# stm32h405-braids.net
KiCad netlist of a schematic drawn in EAGLE
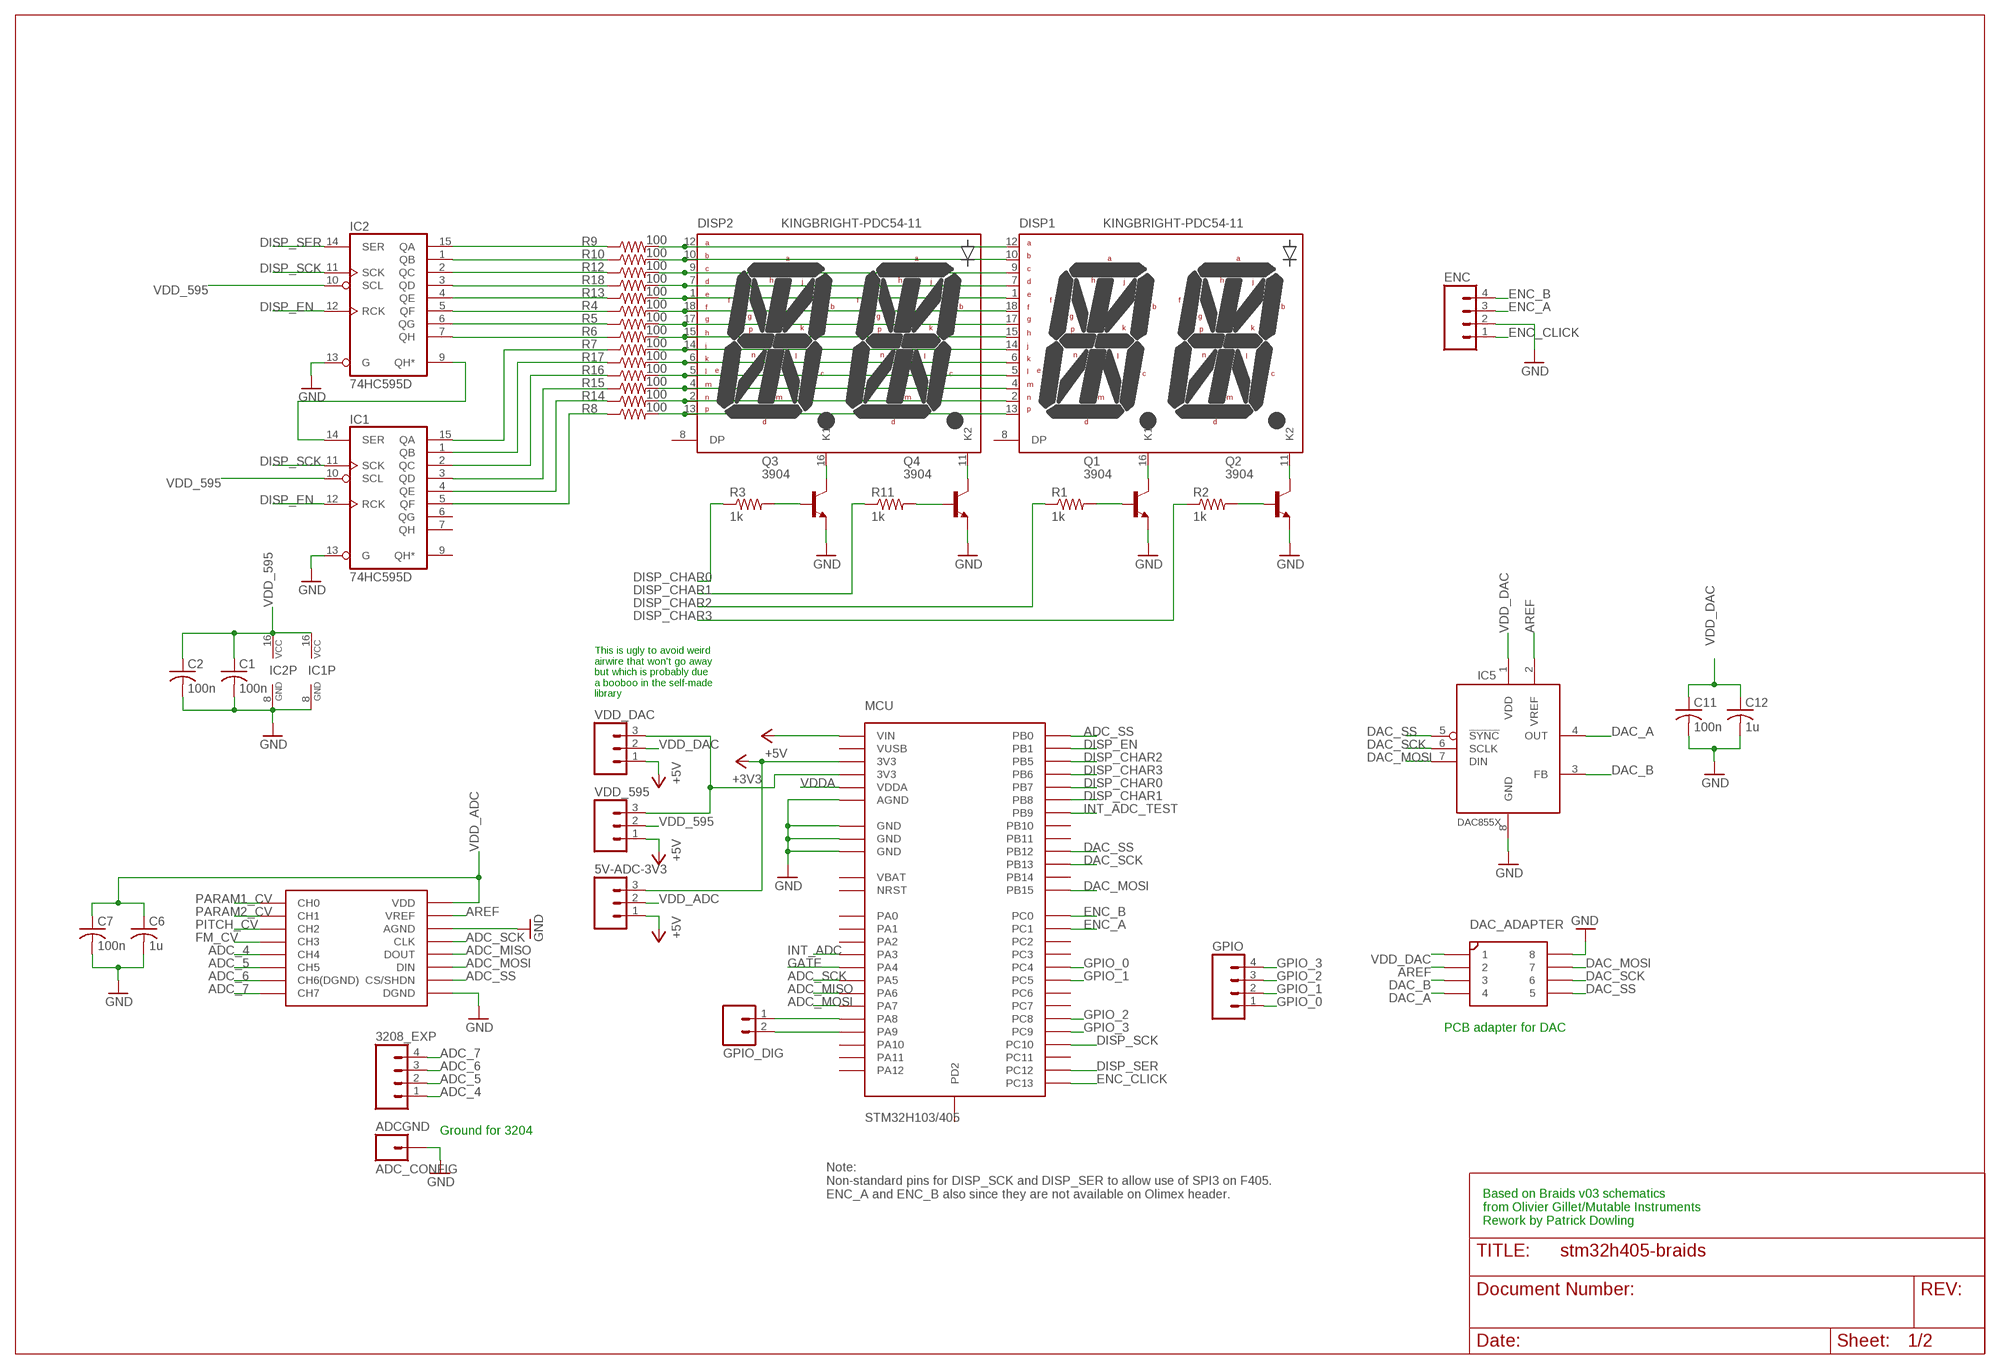
[diagram p0: schematic, sheet 1]
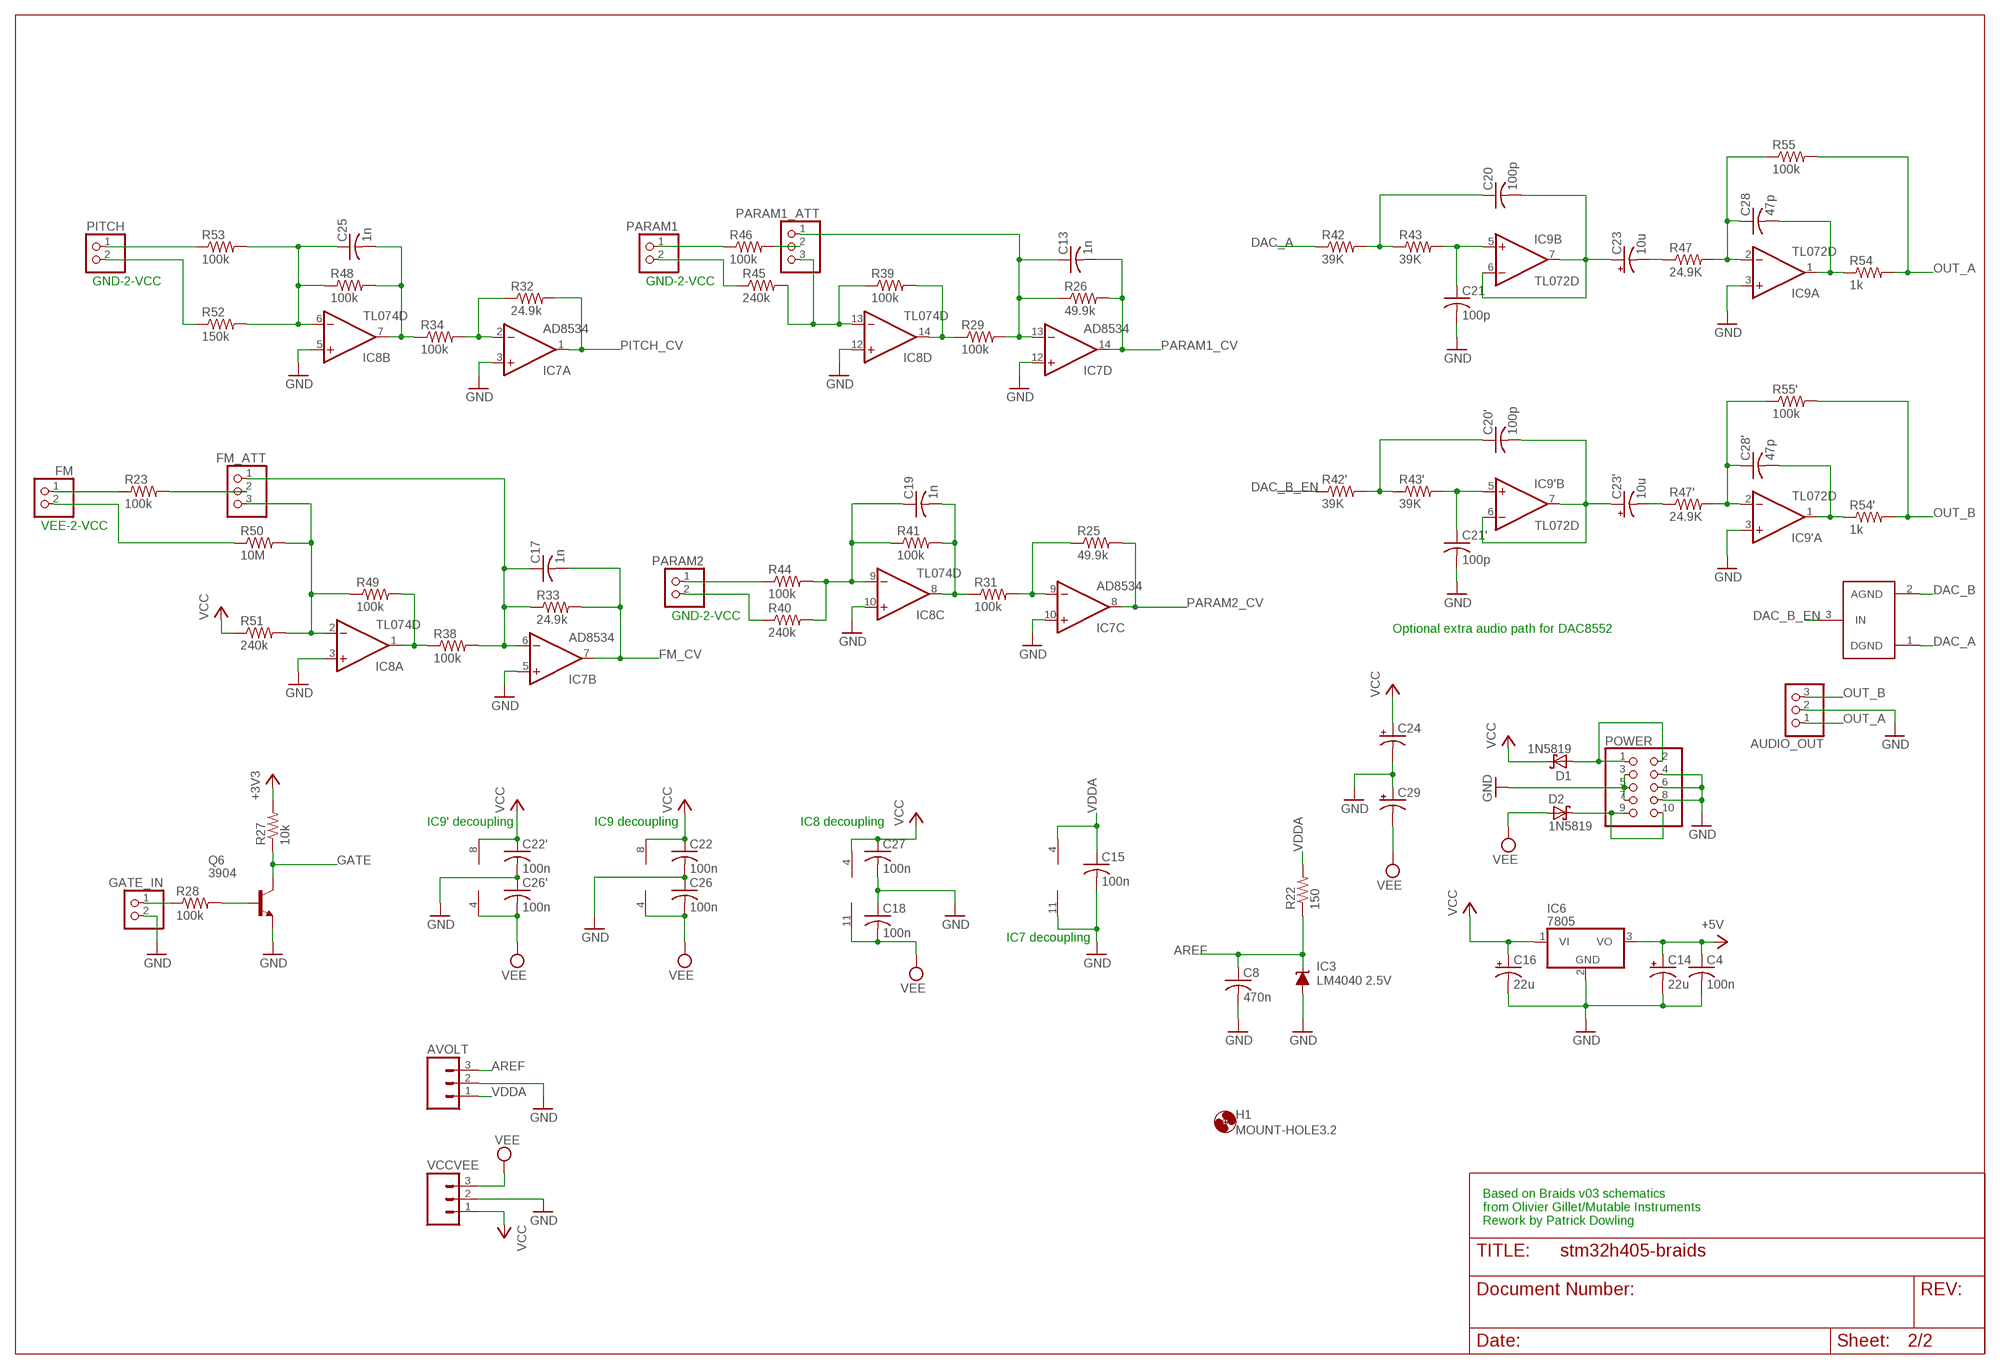
[diagram p1: schematic, sheet 2]

(export (version "E")
  (design (tool "Eeschema 10.0.6"))
  (components
    (comp (ref "AUDIO_OUT")
      (value "PINHD-1X3")
      (footprint "eagle-import:1X03")
      (libsource (lib "eagle-import") (part "PINHD-1X3"))
    )
    (comp (ref "AVOLT")
      (value "M031X03_NO_SILK")
      (footprint "eagle-import:1X03_NO_SILK")
      (libsource (lib "eagle-import") (part "M031X03_NO_SILK"))
    )
    (comp (ref "C4")
      (value "100n")
      (footprint "eagle-import:C025-024X044")
      (libsource (lib "eagle-import") (part "C-US025-024X044"))
    )
    (comp (ref "C8")
      (value "470n")
      (footprint "eagle-import:C0805")
      (libsource (lib "eagle-import") (part "C-USC0805"))
    )
    (comp (ref "C13")
      (value "1n")
      (footprint "eagle-import:C0805")
      (libsource (lib "eagle-import") (part "C-USC0805"))
    )
    (comp (ref "C14")
      (value "22u")
      (footprint "eagle-import:E2,5-6")
      (libsource (lib "eagle-import") (part "CPOL-USE2.5-6"))
    )
    (comp (ref "C15")
      (value "100n")
      (footprint "eagle-import:C0805")
      (libsource (lib "eagle-import") (part "C-USC0805"))
    )
    (comp (ref "C16")
      (value "22u")
      (footprint "eagle-import:E2,5-6")
      (libsource (lib "eagle-import") (part "CPOL-USE2.5-6"))
    )
    (comp (ref "C17")
      (value "1n")
      (footprint "eagle-import:C0805")
      (libsource (lib "eagle-import") (part "C-USC0805"))
    )
    (comp (ref "C18")
      (value "100n")
      (footprint "eagle-import:C0805")
      (libsource (lib "eagle-import") (part "C-USC0805"))
    )
    (comp (ref "C19")
      (value "1n")
      (footprint "eagle-import:C0805")
      (libsource (lib "eagle-import") (part "C-USC0805"))
    )
    (comp (ref "C20")
      (value "100p")
      (footprint "eagle-import:C0805")
      (libsource (lib "eagle-import") (part "C-USC0805"))
    )
    (comp (ref "C20'")
      (value "100p")
      (footprint "eagle-import:C0805")
      (libsource (lib "eagle-import") (part "C-USC0805"))
    )
    (comp (ref "C21")
      (value "100p")
      (footprint "eagle-import:C0805")
      (libsource (lib "eagle-import") (part "C-USC0805"))
    )
    (comp (ref "C21'")
      (value "100p")
      (footprint "eagle-import:C0805")
      (libsource (lib "eagle-import") (part "C-USC0805"))
    )
    (comp (ref "C22")
      (value "100n")
      (footprint "eagle-import:C0805")
      (libsource (lib "eagle-import") (part "C-USC0805"))
    )
    (comp (ref "C22'")
      (value "100n")
      (footprint "eagle-import:C0805")
      (libsource (lib "eagle-import") (part "C-USC0805"))
    )
    (comp (ref "C23")
      (value "10u")
      (footprint "eagle-import:E2-5")
      (libsource (lib "eagle-import") (part "CPOL-USE2-5"))
    )
    (comp (ref "C23'")
      (value "10u")
      (footprint "eagle-import:E2-5")
      (libsource (lib "eagle-import") (part "CPOL-USE2-5"))
    )
    (comp (ref "C24")
      (value "CPOL-USE2.5-6")
      (footprint "eagle-import:E2,5-6")
      (libsource (lib "eagle-import") (part "CPOL-USE2.5-6"))
    )
    (comp (ref "C25")
      (value "1n")
      (footprint "eagle-import:C0805")
      (libsource (lib "eagle-import") (part "C-USC0805"))
    )
    (comp (ref "C26")
      (value "100n")
      (footprint "eagle-import:C0805")
      (libsource (lib "eagle-import") (part "C-USC0805"))
    )
    (comp (ref "C26'")
      (value "100n")
      (footprint "eagle-import:C0805")
      (libsource (lib "eagle-import") (part "C-USC0805"))
    )
    (comp (ref "C27")
      (value "100n")
      (footprint "eagle-import:C0805")
      (libsource (lib "eagle-import") (part "C-USC0805"))
    )
    (comp (ref "C28")
      (value "47p")
      (footprint "eagle-import:C0805")
      (libsource (lib "eagle-import") (part "C-USC0805"))
    )
    (comp (ref "C28'")
      (value "47p")
      (footprint "eagle-import:C0805")
      (libsource (lib "eagle-import") (part "C-USC0805"))
    )
    (comp (ref "C29")
      (value "CPOL-USE2.5-6")
      (footprint "eagle-import:E2,5-6")
      (libsource (lib "eagle-import") (part "CPOL-USE2.5-6"))
    )
    (comp (ref "D1")
      (value "1N5819")
      (footprint "eagle-import:DO41-7.6")
      (libsource (lib "eagle-import") (part "1N5819-B"))
    )
    (comp (ref "D2")
      (value "1N5819")
      (footprint "eagle-import:DO41-7.6")
      (libsource (lib "eagle-import") (part "1N5819-B"))
    )
    (comp (ref "DAC_CONF")
      (value "GND_CONNECT")
      (footprint "eagle-import:GND_CONNECT")
      (libsource (lib "eagle-import") (part "GND_CONNECT"))
    )
    (comp (ref "FM")
      (value "PINHD-1X2")
      (footprint "eagle-import:1X02")
      (libsource (lib "eagle-import") (part "PINHD-1X2"))
    )
    (comp (ref "FM_ATT")
      (value "PINHD-1X3")
      (footprint "eagle-import:1X03")
      (libsource (lib "eagle-import") (part "PINHD-1X3"))
    )
    (comp (ref "GATE_IN")
      (value "PINHD-1X2")
      (footprint "eagle-import:1X02")
      (libsource (lib "eagle-import") (part "PINHD-1X2"))
    )
    (comp (ref "H1")
      (value "MOUNT-HOLE3.2")
      (footprint "eagle-import:3,2")
      (libsource (lib "eagle-import") (part "MOUNT-HOLE3.2"))
    )
    (comp (ref "IC3")
      (value "LM4040 2.5V")
      (footprint "eagle-import:DBZ_R-PDSO-G3")
      (fields (field (name "MPN") "LM4041B12IDBZR"))
      (libsource (lib "eagle-import") (part "LM4041DBZB12"))
    )
    (comp (ref "IC6")
      (value "7805")
      (footprint "eagle-import:TO220V")
      (libsource (lib "eagle-import") (part "78TV05"))
    )
    (comp (ref "IC7")
      (value "AD8534")
      (footprint "eagle-import:SO14")
      (libsource (lib "eagle-import") (part "TL074D"))
    )
    (comp (ref "IC8")
      (value "TL074D")
      (footprint "eagle-import:SO14")
      (libsource (lib "eagle-import") (part "TL074D"))
    )
    (comp (ref "IC9")
      (value "TL072D")
      (footprint "eagle-import:SO08")
      (libsource (lib "eagle-import") (part "TL072D"))
    )
    (comp (ref "IC9'")
      (value "TL072D")
      (footprint "eagle-import:SO08")
      (libsource (lib "eagle-import") (part "TL072D"))
    )
    (comp (ref "PARAM1")
      (value "PINHD-1X2")
      (footprint "eagle-import:1X02")
      (libsource (lib "eagle-import") (part "PINHD-1X2"))
    )
    (comp (ref "PARAM1_ATT")
      (value "PINHD-1X3")
      (footprint "eagle-import:1X03")
      (libsource (lib "eagle-import") (part "PINHD-1X3"))
    )
    (comp (ref "PARAM2")
      (value "PINHD-1X2")
      (footprint "eagle-import:1X02")
      (libsource (lib "eagle-import") (part "PINHD-1X2"))
    )
    (comp (ref "PITCH")
      (value "PINHD-1X2")
      (footprint "eagle-import:1X02")
      (libsource (lib "eagle-import") (part "PINHD-1X2"))
    )
    (comp (ref "POWER")
      (value "PINHD-2X5")
      (footprint "eagle-import:2X05")
      (libsource (lib "eagle-import") (part "PINHD-2X5"))
    )
    (comp (ref "Q6")
      (value "3904")
      (footprint "eagle-import:SOT23-BEC")
      (libsource (lib "eagle-import") (part "-NPN-SOT23-BECMMBT3904LT1"))
    )
    (comp (ref "R22")
      (value "150")
      (footprint "eagle-import:R0805")
      (libsource (lib "eagle-import") (part "R-US_R0805"))
    )
    (comp (ref "R23")
      (value "100k")
      (footprint "eagle-import:R0805")
      (libsource (lib "eagle-import") (part "R-US_R0805"))
    )
    (comp (ref "R25")
      (value "49.9k")
      (footprint "eagle-import:R0805")
      (libsource (lib "eagle-import") (part "R-US_R0805"))
    )
    (comp (ref "R26")
      (value "49.9k")
      (footprint "eagle-import:R0805")
      (libsource (lib "eagle-import") (part "R-US_R0805"))
    )
    (comp (ref "R27")
      (value "10k")
      (footprint "eagle-import:R0805")
      (libsource (lib "eagle-import") (part "R-US_R0805"))
    )
    (comp (ref "R28")
      (value "100k")
      (footprint "eagle-import:R0805")
      (libsource (lib "eagle-import") (part "R-US_R0805"))
    )
    (comp (ref "R29")
      (value "100k")
      (footprint "eagle-import:R0805")
      (libsource (lib "eagle-import") (part "R-US_R0805"))
    )
    (comp (ref "R31")
      (value "100k")
      (footprint "eagle-import:R0805")
      (libsource (lib "eagle-import") (part "R-US_R0805"))
    )
    (comp (ref "R32")
      (value "24.9k")
      (footprint "eagle-import:R0805")
      (libsource (lib "eagle-import") (part "R-US_R0805"))
    )
    (comp (ref "R33")
      (value "24.9k")
      (footprint "eagle-import:R0805")
      (libsource (lib "eagle-import") (part "R-US_R0805"))
    )
    (comp (ref "R34")
      (value "100k")
      (footprint "eagle-import:R0805")
      (libsource (lib "eagle-import") (part "R-US_R0805"))
    )
    (comp (ref "R38")
      (value "100k")
      (footprint "eagle-import:R0805")
      (libsource (lib "eagle-import") (part "R-US_R0805"))
    )
    (comp (ref "R39")
      (value "100k")
      (footprint "eagle-import:R0805")
      (libsource (lib "eagle-import") (part "R-US_R0805"))
    )
    (comp (ref "R40")
      (value "240k")
      (footprint "eagle-import:R0805")
      (libsource (lib "eagle-import") (part "R-US_R0805"))
    )
    (comp (ref "R41")
      (value "100k")
      (footprint "eagle-import:R0805")
      (libsource (lib "eagle-import") (part "R-US_R0805"))
    )
    (comp (ref "R42")
      (value "39K")
      (footprint "eagle-import:R0805")
      (libsource (lib "eagle-import") (part "R-US_R0805"))
    )
    (comp (ref "R42'")
      (value "39K")
      (footprint "eagle-import:R0805")
      (libsource (lib "eagle-import") (part "R-US_R0805"))
    )
    (comp (ref "R43")
      (value "39K")
      (footprint "eagle-import:R0805")
      (libsource (lib "eagle-import") (part "R-US_R0805"))
    )
    (comp (ref "R43'")
      (value "39K")
      (footprint "eagle-import:R0805")
      (libsource (lib "eagle-import") (part "R-US_R0805"))
    )
    (comp (ref "R44")
      (value "100k")
      (footprint "eagle-import:R0805")
      (libsource (lib "eagle-import") (part "R-US_R0805"))
    )
    (comp (ref "R45")
      (value "240k")
      (footprint "eagle-import:R0805")
      (libsource (lib "eagle-import") (part "R-US_R0805"))
    )
    (comp (ref "R46")
      (value "100k")
      (footprint "eagle-import:R0805")
      (libsource (lib "eagle-import") (part "R-US_R0805"))
    )
    (comp (ref "R47")
      (value "24.9K")
      (footprint "eagle-import:R0805")
      (libsource (lib "eagle-import") (part "R-US_R0805"))
    )
    (comp (ref "R47'")
      (value "24.9K")
      (footprint "eagle-import:R0805")
      (libsource (lib "eagle-import") (part "R-US_R0805"))
    )
    (comp (ref "R48")
      (value "100k")
      (footprint "eagle-import:R0805")
      (libsource (lib "eagle-import") (part "R-US_R0805"))
    )
    (comp (ref "R49")
      (value "100k")
      (footprint "eagle-import:R0805")
      (libsource (lib "eagle-import") (part "R-US_R0805"))
    )
    (comp (ref "R50")
      (value "10M")
      (footprint "eagle-import:R0805")
      (libsource (lib "eagle-import") (part "R-US_R0805"))
    )
    (comp (ref "R51")
      (value "240k")
      (footprint "eagle-import:R0805")
      (libsource (lib "eagle-import") (part "R-US_R0805"))
    )
    (comp (ref "R52")
      (value "150k")
      (footprint "eagle-import:R0805")
      (libsource (lib "eagle-import") (part "R-US_R0805"))
    )
    (comp (ref "R53")
      (value "100k")
      (footprint "eagle-import:R0805")
      (libsource (lib "eagle-import") (part "R-US_R0805"))
    )
    (comp (ref "R54")
      (value "1k")
      (footprint "eagle-import:R0805")
      (libsource (lib "eagle-import") (part "R-US_R0805"))
    )
    (comp (ref "R54'")
      (value "1k")
      (footprint "eagle-import:R0805")
      (libsource (lib "eagle-import") (part "R-US_R0805"))
    )
    (comp (ref "R55")
      (value "100k")
      (footprint "eagle-import:R0805")
      (libsource (lib "eagle-import") (part "R-US_R0805"))
    )
    (comp (ref "R55'")
      (value "100k")
      (footprint "eagle-import:R0805")
      (libsource (lib "eagle-import") (part "R-US_R0805"))
    )
    (comp (ref "VCCVEE")
      (value "M031X03_NO_SILK")
      (footprint "eagle-import:1X03_NO_SILK")
      (libsource (lib "eagle-import") (part "M031X03_NO_SILK"))
    )
    (comp (ref "5V-ADC-3V3")
      (value "M031X03_NO_SILK")
      (footprint "eagle-import:1X03_NO_SILK")
      (libsource (lib "eagle-import") (part "M031X03_NO_SILK"))
    )
    (comp (ref "3208_EXP")
      (value "M041X04_NO_SILK")
      (footprint "eagle-import:1X04_NO_SILK")
      (libsource (lib "eagle-import") (part "M041X04_NO_SILK"))
    )
    (comp (ref "ADCGND")
      (value "ADC_CONFIG")
      (footprint "eagle-import:1X01NS-KIT")
      (libsource (lib "eagle-import") (part "M01NOSILK-KIT"))
    )
    (comp (ref "C1")
      (value "100n")
      (footprint "eagle-import:C0805")
      (libsource (lib "eagle-import") (part "C-USC0805"))
    )
    (comp (ref "C2")
      (value "100n")
      (footprint "eagle-import:C0805")
      (libsource (lib "eagle-import") (part "C-USC0805"))
    )
    (comp (ref "C6")
      (value "1u")
      (footprint "eagle-import:C0805")
      (libsource (lib "eagle-import") (part "C-USC0805"))
    )
    (comp (ref "C7")
      (value "100n")
      (footprint "eagle-import:C0805")
      (libsource (lib "eagle-import") (part "C-USC0805"))
    )
    (comp (ref "C11")
      (value "100n")
      (footprint "eagle-import:C0805")
      (libsource (lib "eagle-import") (part "C-USC0805"))
    )
    (comp (ref "C12")
      (value "1u")
      (footprint "eagle-import:C0805")
      (libsource (lib "eagle-import") (part "C-USC0805"))
    )
    (comp (ref "DAC_ADAPTER")
      (value "DILSOP")
      (footprint "eagle-import:DILSOP")
      (libsource (lib "eagle-import") (part "DILSOP"))
    )
    (comp (ref "DISP1")
      (value "KINGBRIGHT-PDC54-11")
      (footprint "eagle-import:PDC54")
      (libsource (lib "eagle-import") (part "KINGBRIGHT-PDC54-11"))
    )
    (comp (ref "DISP2")
      (value "KINGBRIGHT-PDC54-11")
      (footprint "eagle-import:PDC54")
      (libsource (lib "eagle-import") (part "KINGBRIGHT-PDC54-11"))
    )
    (comp (ref "ENC")
      (value "M04PTH")
      (footprint "eagle-import:1X04")
      (libsource (lib "eagle-import") (part "M04PTH"))
    )
    (comp (ref "GPIO")
      (value "M04NO_SILK_ALL_ROUND")
      (footprint "eagle-import:1X04_NO_SILK_ALL_ROUND")
      (libsource (lib "eagle-import") (part "M04NO_SILK_ALL_ROUND"))
    )
    (comp (ref "GPIO_DIG")
      (value "M02PTH")
      (footprint "eagle-import:1X02")
      (libsource (lib "eagle-import") (part "M02PTH"))
    )
    (comp (ref "IC1")
      (value "74HC595D")
      (footprint "eagle-import:SO16")
      (libsource (lib "eagle-import") (part "74595DHC"))
    )
    (comp (ref "IC2")
      (value "74HC595D")
      (footprint "eagle-import:SO16")
      (libsource (lib "eagle-import") (part "74595DHC"))
    )
    (comp (ref "IC4")
      (value "MCP3204/3208")
      (footprint "eagle-import:DIL16")
      (libsource (lib "eagle-import") (part "MCP320X"))
    )
    (comp (ref "IC5")
      (value "DAC855X")
      (footprint "eagle-import:MSOP-8")
      (libsource (lib "eagle-import") (part "DAC855X"))
    )
    (comp (ref "MCU")
      (value "STM32H103/405")
      (footprint "eagle-import:STM32H103")
      (libsource (lib "eagle-import") (part "STM32H103"))
    )
    (comp (ref "Q1")
      (value "3904")
      (footprint "eagle-import:SOT23-BEC")
      (libsource (lib "eagle-import") (part "-NPN-SOT23-BECMMBT3904LT1"))
    )
    (comp (ref "Q2")
      (value "3904")
      (footprint "eagle-import:SOT23-BEC")
      (libsource (lib "eagle-import") (part "-NPN-SOT23-BECMMBT3904LT1"))
    )
    (comp (ref "Q3")
      (value "3904")
      (footprint "eagle-import:SOT23-BEC")
      (libsource (lib "eagle-import") (part "-NPN-SOT23-BECMMBT3904LT1"))
    )
    (comp (ref "Q4")
      (value "3904")
      (footprint "eagle-import:SOT23-BEC")
      (libsource (lib "eagle-import") (part "-NPN-SOT23-BECMMBT3904LT1"))
    )
    (comp (ref "R1")
      (value "1k")
      (footprint "eagle-import:R0805")
      (libsource (lib "eagle-import") (part "R-US_R0805"))
    )
    (comp (ref "R2")
      (value "1k")
      (footprint "eagle-import:R0805")
      (libsource (lib "eagle-import") (part "R-US_R0805"))
    )
    (comp (ref "R3")
      (value "1k")
      (footprint "eagle-import:R0805")
      (libsource (lib "eagle-import") (part "R-US_R0805"))
    )
    (comp (ref "R4")
      (value "100")
      (footprint "eagle-import:R0603")
      (libsource (lib "eagle-import") (part "R-US_R0603"))
    )
    (comp (ref "R5")
      (value "100")
      (footprint "eagle-import:R0603")
      (libsource (lib "eagle-import") (part "R-US_R0603"))
    )
    (comp (ref "R6")
      (value "100")
      (footprint "eagle-import:R0603")
      (libsource (lib "eagle-import") (part "R-US_R0603"))
    )
    (comp (ref "R7")
      (value "100")
      (footprint "eagle-import:R0603")
      (libsource (lib "eagle-import") (part "R-US_R0603"))
    )
    (comp (ref "R8")
      (value "100")
      (footprint "eagle-import:R0603")
      (libsource (lib "eagle-import") (part "R-US_R0603"))
    )
    (comp (ref "R9")
      (value "100")
      (footprint "eagle-import:R0603")
      (libsource (lib "eagle-import") (part "R-US_R0603"))
    )
    (comp (ref "R10")
      (value "100")
      (footprint "eagle-import:R0603")
      (libsource (lib "eagle-import") (part "R-US_R0603"))
    )
    (comp (ref "R11")
      (value "1k")
      (footprint "eagle-import:R0805")
      (libsource (lib "eagle-import") (part "R-US_R0805"))
    )
    (comp (ref "R12")
      (value "100")
      (footprint "eagle-import:R0603")
      (libsource (lib "eagle-import") (part "R-US_R0603"))
    )
    (comp (ref "R13")
      (value "100")
      (footprint "eagle-import:R0603")
      (libsource (lib "eagle-import") (part "R-US_R0603"))
    )
    (comp (ref "R14")
      (value "100")
      (footprint "eagle-import:R0603")
      (libsource (lib "eagle-import") (part "R-US_R0603"))
    )
    (comp (ref "R15")
      (value "100")
      (footprint "eagle-import:R0603")
      (libsource (lib "eagle-import") (part "R-US_R0603"))
    )
    (comp (ref "R16")
      (value "100")
      (footprint "eagle-import:R0603")
      (libsource (lib "eagle-import") (part "R-US_R0603"))
    )
    (comp (ref "R17")
      (value "100")
      (footprint "eagle-import:R0603")
      (libsource (lib "eagle-import") (part "R-US_R0603"))
    )
    (comp (ref "R18")
      (value "100")
      (footprint "eagle-import:R0603")
      (libsource (lib "eagle-import") (part "R-US_R0603"))
    )
    (comp (ref "VDD_595")
      (value "M031X03_NO_SILK")
      (footprint "eagle-import:1X03_NO_SILK")
      (libsource (lib "eagle-import") (part "M031X03_NO_SILK"))
    )
    (comp (ref "VDD_DAC")
      (value "M031X03_NO_SILK")
      (footprint "eagle-import:1X03_NO_SILK")
      (libsource (lib "eagle-import") (part "M031X03_NO_SILK"))
    )
  )
  (nets
    (net (code "1") (name "+3V3") (class "Default")
      (node (ref "5V-ADC-3V3") (pin "3") (pinfunction "3_3") (pintype "passive"))
      (node (ref "MCU") (pin "EXT1-5") (pinfunction "3V3_EXT1-5") (pintype "bidirectional"))
      (node (ref "R27") (pin "2") (pinfunction "2_2") (pintype "passive"))
    )
    (net (code "2") (name "+5V") (class "Default")
      (node (ref "5V-ADC-3V3") (pin "1") (pinfunction "1_1") (pintype "passive"))
      (node (ref "C14") (pin "+") (pinfunction "+_+") (pintype "passive"))
      (node (ref "C4") (pin "1") (pinfunction "1_1") (pintype "passive"))
      (node (ref "IC6") (pin "3") (pinfunction "VO_3") (pintype "passive"))
      (node (ref "MCU") (pin "EXT2-26") (pinfunction "VIN_EXT2-26") (pintype "bidirectional"))
      (node (ref "VDD_595") (pin "1") (pinfunction "1_1") (pintype "passive"))
      (node (ref "VDD_DAC") (pin "1") (pinfunction "1_1") (pintype "passive"))
    )
    (net (code "3") (name "ADC_4") (class "Default")
      (node (ref "3208_EXP") (pin "1") (pinfunction "1_1") (pintype "passive"))
      (node (ref "IC4") (pin "5") (pinfunction "CH4_5") (pintype "bidirectional"))
    )
    (net (code "4") (name "ADC_5") (class "Default")
      (node (ref "3208_EXP") (pin "2") (pinfunction "2_2") (pintype "passive"))
      (node (ref "IC4") (pin "6") (pinfunction "CH5_6") (pintype "bidirectional"))
    )
    (net (code "5") (name "ADC_6") (class "Default")
      (node (ref "3208_EXP") (pin "3") (pinfunction "3_3") (pintype "passive"))
      (node (ref "IC4") (pin "7") (pinfunction "CH6(DGND)_7") (pintype "bidirectional"))
    )
    (net (code "6") (name "ADC_7") (class "Default")
      (node (ref "3208_EXP") (pin "4") (pinfunction "4_4") (pintype "passive"))
      (node (ref "IC4") (pin "8") (pinfunction "CH7_8") (pintype "bidirectional"))
    )
    (net (code "7") (name "ADC_MISO") (class "Default")
      (node (ref "IC4") (pin "12") (pinfunction "DOUT_12") (pintype "bidirectional"))
      (node (ref "MCU") (pin "EXT1-14") (pinfunction "PA6_EXT1-14") (pintype "bidirectional"))
    )
    (net (code "8") (name "ADC_MOSI") (class "Default")
      (node (ref "IC4") (pin "11") (pinfunction "DIN_11") (pintype "bidirectional"))
      (node (ref "MCU") (pin "EXT1-22") (pinfunction "PA7_EXT1-22") (pintype "bidirectional"))
    )
    (net (code "9") (name "ADC_SCK") (class "Default")
      (node (ref "IC4") (pin "13") (pinfunction "CLK_13") (pintype "bidirectional"))
      (node (ref "MCU") (pin "EXT1-18") (pinfunction "PA5_EXT1-18") (pintype "bidirectional"))
    )
    (net (code "10") (name "ADC_SS") (class "Default")
      (node (ref "IC4") (pin "10") (pinfunction "CS/SHDN_10") (pintype "bidirectional"))
      (node (ref "MCU") (pin "EXT1-21") (pinfunction "PB0_EXT1-21") (pintype "bidirectional"))
    )
    (net (code "11") (name "AREF") (class "Default")
      (node (ref "AVOLT") (pin "3") (pinfunction "3_3") (pintype "passive"))
      (node (ref "C8") (pin "1") (pinfunction "1_1") (pintype "passive"))
      (node (ref "DAC_ADAPTER") (pin "P$2") (pinfunction "2_P$2") (pintype "bidirectional"))
      (node (ref "IC3") (pin "1") (pinfunction "C_1") (pintype "passive"))
      (node (ref "IC4") (pin "15") (pinfunction "VREF_15") (pintype "bidirectional"))
      (node (ref "IC5") (pin "2") (pinfunction "VREF_2") (pintype "power_in"))
      (node (ref "R22") (pin "1") (pinfunction "1_1") (pintype "passive"))
    )
    (net (code "12") (name "DAC_A") (class "Default")
      (node (ref "DAC_ADAPTER") (pin "P$4") (pinfunction "4_P$4") (pintype "bidirectional"))
      (node (ref "DAC_CONF") (pin "1") (pinfunction "DGND_1") (pintype "bidirectional"))
      (node (ref "IC5") (pin "4") (pinfunction "OUT_4") (pintype "output"))
      (node (ref "R42") (pin "1") (pinfunction "1_1") (pintype "passive"))
    )
    (net (code "13") (name "DAC_B") (class "Default")
      (node (ref "DAC_ADAPTER") (pin "P$3") (pinfunction "3_P$3") (pintype "bidirectional"))
      (node (ref "DAC_CONF") (pin "2") (pinfunction "AGND_2") (pintype "bidirectional"))
      (node (ref "IC5") (pin "3") (pinfunction "FB_3") (pintype "input"))
    )
    (net (code "14") (name "DAC_B_EN") (class "Default")
      (node (ref "DAC_CONF") (pin "3") (pinfunction "IN_3") (pintype "bidirectional"))
      (node (ref "R42'") (pin "1") (pinfunction "1_1") (pintype "passive"))
    )
    (net (code "15") (name "DAC_MOSI") (class "Default")
      (node (ref "DAC_ADAPTER") (pin "P$7") (pinfunction "7_P$7") (pintype "bidirectional"))
      (node (ref "IC5") (pin "7") (pinfunction "DIN_7") (pintype "bidirectional"))
      (node (ref "MCU") (pin "EXT2-19") (pinfunction "PB15_EXT2-19") (pintype "bidirectional"))
    )
    (net (code "16") (name "DAC_SCK") (class "Default")
      (node (ref "DAC_ADAPTER") (pin "P$6") (pinfunction "6_P$6") (pintype "bidirectional"))
      (node (ref "IC5") (pin "6") (pinfunction "SCLK_6") (pintype "bidirectional"))
      (node (ref "MCU") (pin "EXT2-16") (pinfunction "PB13_EXT2-16") (pintype "bidirectional"))
    )
    (net (code "17") (name "DAC_SS") (class "Default")
      (node (ref "DAC_ADAPTER") (pin "P$5") (pinfunction "5_P$5") (pintype "bidirectional"))
      (node (ref "IC5") (pin "5") (pinfunction "~{SYNC}_5") (pintype "bidirectional"))
      (node (ref "MCU") (pin "EXT2-17") (pinfunction "PB12_EXT2-17") (pintype "bidirectional"))
    )
    (net (code "18") (name "DISP_CHAR0") (class "Default")
      (node (ref "MCU") (pin "EXT1-15") (pinfunction "PB7_EXT1-15") (pintype "bidirectional"))
      (node (ref "R3") (pin "1") (pinfunction "1_1") (pintype "passive"))
    )
    (net (code "19") (name "DISP_CHAR1") (class "Default")
      (node (ref "MCU") (pin "EXT1-16") (pinfunction "PB8_EXT1-16") (pintype "bidirectional"))
      (node (ref "R11") (pin "1") (pinfunction "1_1") (pintype "passive"))
    )
    (net (code "20") (name "DISP_CHAR2") (class "Default")
      (node (ref "MCU") (pin "EXT1-12") (pinfunction "PB5_EXT1-12") (pintype "bidirectional"))
      (node (ref "R1") (pin "1") (pinfunction "1_1") (pintype "passive"))
    )
    (net (code "21") (name "DISP_CHAR3") (class "Default")
      (node (ref "MCU") (pin "EXT1-13") (pinfunction "PB6_EXT1-13") (pintype "bidirectional"))
      (node (ref "R2") (pin "1") (pinfunction "1_1") (pintype "passive"))
    )
    (net (code "22") (name "DISP_EN") (class "Default")
      (node (ref "IC1") (pin "12") (pinfunction "RCK_12") (pintype "input"))
      (node (ref "IC2") (pin "12") (pinfunction "RCK_12") (pintype "input"))
      (node (ref "MCU") (pin "EXT1-26") (pinfunction "PB1_EXT1-26") (pintype "bidirectional"))
    )
    (net (code "23") (name "DISP_SCK") (class "Default")
      (node (ref "IC1") (pin "11") (pinfunction "SCK_11") (pintype "input"))
      (node (ref "IC2") (pin "11") (pinfunction "SCK_11") (pintype "input"))
      (node (ref "MCU") (pin "EXT1-8") (pinfunction "PC10_EXT1-8") (pintype "bidirectional"))
    )
    (net (code "24") (name "DISP_SER") (class "Default")
      (node (ref "IC2") (pin "14") (pinfunction "SER_14") (pintype "input"))
      (node (ref "MCU") (pin "EXT1-10") (pinfunction "PC12_EXT1-10") (pintype "bidirectional"))
    )
    (net (code "25") (name "ENC_A") (class "Default")
      (node (ref "ENC") (pin "3") (pinfunction "3_3") (pintype "passive"))
      (node (ref "MCU") (pin "EXT1-20") (pinfunction "PC1_EXT1-20") (pintype "bidirectional"))
    )
    (net (code "26") (name "ENC_B") (class "Default")
      (node (ref "ENC") (pin "4") (pinfunction "4_4") (pintype "passive"))
      (node (ref "MCU") (pin "EXT1-19") (pinfunction "PC0_EXT1-19") (pintype "bidirectional"))
    )
    (net (code "27") (name "ENC_CLICK") (class "Default")
      (node (ref "ENC") (pin "1") (pinfunction "1_1") (pintype "passive"))
      (node (ref "MCU") (pin "EXT1-24") (pinfunction "PC13_EXT1-24") (pintype "bidirectional"))
    )
    (net (code "28") (name "FM_CV") (class "Default")
      (node (ref "C17") (pin "2") (pinfunction "2_2") (pintype "passive"))
      (node (ref "IC4") (pin "4") (pinfunction "CH3_4") (pintype "bidirectional"))
      (node (ref "IC7") (pin "7") (pinfunction "OUT_7") (pintype "output"))
      (node (ref "R33") (pin "2") (pinfunction "2_2") (pintype "passive"))
    )
    (net (code "29") (name "GATE") (class "Default")
      (node (ref "MCU") (pin "EXT2-11") (pinfunction "PA4_EXT2-11") (pintype "bidirectional"))
      (node (ref "Q6") (pin "C") (pinfunction "C_C") (pintype "passive"))
      (node (ref "R27") (pin "1") (pinfunction "1_1") (pintype "passive"))
    )
    (net (code "30") (name "GND") (class "Default")
      (node (ref "ADCGND") (pin "1") (pinfunction "1_1") (pintype "passive"))
      (node (ref "AUDIO_OUT") (pin "2") (pinfunction "2_2") (pintype "passive"))
      (node (ref "AVOLT") (pin "2") (pinfunction "2_2") (pintype "passive"))
      (node (ref "C1") (pin "2") (pinfunction "2_2") (pintype "passive"))
      (node (ref "C11") (pin "2") (pinfunction "2_2") (pintype "passive"))
      (node (ref "C12") (pin "2") (pinfunction "2_2") (pintype "passive"))
      (node (ref "C14") (pin "-") (pinfunction "-_-") (pintype "passive"))
      (node (ref "C15") (pin "2") (pinfunction "2_2") (pintype "passive"))
      (node (ref "C16") (pin "-") (pinfunction "-_-") (pintype "passive"))
      (node (ref "C18") (pin "1") (pinfunction "1_1") (pintype "passive"))
      (node (ref "C2") (pin "2") (pinfunction "2_2") (pintype "passive"))
      (node (ref "C21") (pin "2") (pinfunction "2_2") (pintype "passive"))
      (node (ref "C21'") (pin "2") (pinfunction "2_2") (pintype "passive"))
      (node (ref "C22") (pin "2") (pinfunction "2_2") (pintype "passive"))
      (node (ref "C22'") (pin "2") (pinfunction "2_2") (pintype "passive"))
      (node (ref "C24") (pin "-") (pinfunction "-_-") (pintype "passive"))
      (node (ref "C26") (pin "1") (pinfunction "1_1") (pintype "passive"))
      (node (ref "C26'") (pin "1") (pinfunction "1_1") (pintype "passive"))
      (node (ref "C27") (pin "2") (pinfunction "2_2") (pintype "passive"))
      (node (ref "C29") (pin "+") (pinfunction "+_+") (pintype "passive"))
      (node (ref "C4") (pin "2") (pinfunction "2_2") (pintype "passive"))
      (node (ref "C6") (pin "2") (pinfunction "2_2") (pintype "passive"))
      (node (ref "C7") (pin "2") (pinfunction "2_2") (pintype "passive"))
      (node (ref "C8") (pin "2") (pinfunction "2_2") (pintype "passive"))
      (node (ref "DAC_ADAPTER") (pin "P$8") (pinfunction "8_P$8") (pintype "bidirectional"))
      (node (ref "ENC") (pin "2") (pinfunction "2_2") (pintype "passive"))
      (node (ref "GATE_IN") (pin "2") (pinfunction "2_2") (pintype "passive"))
      (node (ref "IC1") (pin "13") (pinfunction "G_13") (pintype "input"))
      (node (ref "IC1") (pin "8") (pinfunction "GND_8") (pintype "power_in"))
      (node (ref "IC2") (pin "13") (pinfunction "G_13") (pintype "input"))
      (node (ref "IC2") (pin "8") (pinfunction "GND_8") (pintype "power_in"))
      (node (ref "IC3") (pin "2") (pinfunction "A_2") (pintype "passive"))
      (node (ref "IC4") (pin "14") (pinfunction "AGND_14") (pintype "bidirectional"))
      (node (ref "IC4") (pin "9") (pinfunction "DGND_9") (pintype "bidirectional"))
      (node (ref "IC5") (pin "8") (pinfunction "GND_8") (pintype "power_in"))
      (node (ref "IC6") (pin "2") (pinfunction "GND_2") (pintype "passive"))
      (node (ref "IC7") (pin "10") (pinfunction "+IN_10") (pintype "input"))
      (node (ref "IC7") (pin "11") (pinfunction "V-_11") (pintype "power_in"))
      (node (ref "IC7") (pin "12") (pinfunction "+IN_12") (pintype "input"))
      (node (ref "IC7") (pin "3") (pinfunction "+IN_3") (pintype "input"))
      (node (ref "IC7") (pin "5") (pinfunction "+IN_5") (pintype "input"))
      (node (ref "IC8") (pin "10") (pinfunction "+IN_10") (pintype "input"))
      (node (ref "IC8") (pin "12") (pinfunction "+IN_12") (pintype "input"))
      (node (ref "IC8") (pin "3") (pinfunction "+IN_3") (pintype "input"))
      (node (ref "IC8") (pin "5") (pinfunction "+IN_5") (pintype "input"))
      (node (ref "IC9") (pin "3") (pinfunction "+IN_3") (pintype "input"))
      (node (ref "IC9'") (pin "3") (pinfunction "+IN_3") (pintype "input"))
      (node (ref "MCU") (pin "EXT1-6") (pinfunction "GND_EXT1-6") (pintype "bidirectional"))
      (node (ref "MCU") (pin "EXT2-25") (pinfunction "GND_EXT2-25") (pintype "bidirectional"))
      (node (ref "MCU") (pin "EXT2-3") (pinfunction "AGND_EXT2-3") (pintype "bidirectional"))
      (node (ref "MCU") (pin "EXT2-6") (pinfunction "GND_EXT2-6") (pintype "bidirectional"))
      (node (ref "POWER") (pin "3") (pinfunction "3_3") (pintype "passive"))
      (node (ref "POWER") (pin "4") (pinfunction "4_4") (pintype "passive"))
      (node (ref "POWER") (pin "5") (pinfunction "5_5") (pintype "passive"))
      (node (ref "POWER") (pin "6") (pinfunction "6_6") (pintype "passive"))
      (node (ref "POWER") (pin "7") (pinfunction "7_7") (pintype "passive"))
      (node (ref "POWER") (pin "8") (pinfunction "8_8") (pintype "passive"))
      (node (ref "Q1") (pin "E") (pinfunction "E_E") (pintype "passive"))
      (node (ref "Q2") (pin "E") (pinfunction "E_E") (pintype "passive"))
      (node (ref "Q3") (pin "E") (pinfunction "E_E") (pintype "passive"))
      (node (ref "Q4") (pin "E") (pinfunction "E_E") (pintype "passive"))
      (node (ref "Q6") (pin "E") (pinfunction "E_E") (pintype "passive"))
      (node (ref "VCCVEE") (pin "2") (pinfunction "2_2") (pintype "passive"))
    )
    (net (code "31") (name "GPIO_0") (class "Default")
      (node (ref "GPIO") (pin "1") (pinfunction "1_1") (pintype "passive"))
      (node (ref "MCU") (pin "EXT2-12") (pinfunction "PC4_EXT2-12") (pintype "bidirectional"))
    )
    (net (code "32") (name "GPIO_1") (class "Default")
      (node (ref "GPIO") (pin "2") (pinfunction "2_2") (pintype "passive"))
      (node (ref "MCU") (pin "EXT2-13") (pinfunction "PC5_EXT2-13") (pintype "bidirectional"))
    )
    (net (code "33") (name "GPIO_2") (class "Default")
      (node (ref "GPIO") (pin "3") (pinfunction "3_3") (pintype "passive"))
      (node (ref "MCU") (pin "EXT2-22") (pinfunction "PC8_EXT2-22") (pintype "bidirectional"))
    )
    (net (code "34") (name "GPIO_3") (class "Default")
      (node (ref "GPIO") (pin "4") (pinfunction "4_4") (pintype "passive"))
      (node (ref "MCU") (pin "EXT2-24") (pinfunction "PC9_EXT2-24") (pintype "bidirectional"))
    )
    (net (code "35") (name "INT_ADC") (class "Default")
      (node (ref "MCU") (pin "EXT2-10") (pinfunction "PA3_EXT2-10") (pintype "bidirectional"))
    )
    (net (code "36") (name "INT_ADC_TEST") (class "Default")
      (node (ref "MCU") (pin "EXT1-17") (pinfunction "PB9_EXT1-17") (pintype "bidirectional"))
    )
    (net (code "37") (name "Net-(C20'-Pad1)") (class "Default")
      (node (ref "C20'") (pin "1") (pinfunction "1_1") (pintype "passive"))
      (node (ref "R42'") (pin "2") (pinfunction "2_2") (pintype "passive"))
      (node (ref "R43'") (pin "1") (pinfunction "1_1") (pintype "passive"))
    )
    (net (code "38") (name "Net-(C20-Pad1)") (class "Default")
      (node (ref "C20") (pin "1") (pinfunction "1_1") (pintype "passive"))
      (node (ref "R42") (pin "2") (pinfunction "2_2") (pintype "passive"))
      (node (ref "R43") (pin "1") (pinfunction "1_1") (pintype "passive"))
    )
    (net (code "39") (name "Net-(C23'-Pad-)") (class "Default")
      (node (ref "C23'") (pin "-") (pinfunction "-_-") (pintype "passive"))
      (node (ref "R47'") (pin "1") (pinfunction "1_1") (pintype "passive"))
    )
    (net (code "40") (name "Net-(C23-Pad-)") (class "Default")
      (node (ref "C23") (pin "-") (pinfunction "-_-") (pintype "passive"))
      (node (ref "R47") (pin "1") (pinfunction "1_1") (pintype "passive"))
    )
    (net (code "41") (name "Net-(D1-PadA)") (class "Default")
      (node (ref "D1") (pin "A") (pinfunction "A_A") (pintype "passive"))
      (node (ref "POWER") (pin "1") (pinfunction "1_1") (pintype "passive"))
      (node (ref "POWER") (pin "2") (pinfunction "2_2") (pintype "passive"))
    )
    (net (code "42") (name "Net-(D2-PadC)") (class "Default")
      (node (ref "D2") (pin "C") (pinfunction "C_C") (pintype "passive"))
      (node (ref "POWER") (pin "10") (pinfunction "10_10") (pintype "passive"))
      (node (ref "POWER") (pin "9") (pinfunction "9_9") (pintype "passive"))
    )
    (net (code "43") (name "Net-(DISP1-A)") (class "Default")
      (node (ref "DISP1") (pin "12") (pinfunction "A_12") (pintype "passive"))
      (node (ref "DISP2") (pin "12") (pinfunction "A_12") (pintype "passive"))
      (node (ref "R9") (pin "2") (pinfunction "2_2") (pintype "passive"))
    )
    (net (code "44") (name "Net-(DISP1-B)") (class "Default")
      (node (ref "DISP1") (pin "10") (pinfunction "B_10") (pintype "passive"))
      (node (ref "DISP2") (pin "10") (pinfunction "B_10") (pintype "passive"))
      (node (ref "R10") (pin "2") (pinfunction "2_2") (pintype "passive"))
    )
    (net (code "45") (name "Net-(DISP1-C)") (class "Default")
      (node (ref "DISP1") (pin "9") (pinfunction "C_9") (pintype "passive"))
      (node (ref "DISP2") (pin "9") (pinfunction "C_9") (pintype "passive"))
      (node (ref "R12") (pin "2") (pinfunction "2_2") (pintype "passive"))
    )
    (net (code "46") (name "Net-(DISP1-D)") (class "Default")
      (node (ref "DISP1") (pin "7") (pinfunction "D_7") (pintype "passive"))
      (node (ref "DISP2") (pin "7") (pinfunction "D_7") (pintype "passive"))
      (node (ref "R18") (pin "2") (pinfunction "2_2") (pintype "passive"))
    )
    (net (code "47") (name "Net-(DISP1-E)") (class "Default")
      (node (ref "DISP1") (pin "1") (pinfunction "E_1") (pintype "passive"))
      (node (ref "DISP2") (pin "1") (pinfunction "E_1") (pintype "passive"))
      (node (ref "R13") (pin "2") (pinfunction "2_2") (pintype "passive"))
    )
    (net (code "48") (name "Net-(DISP1-F)") (class "Default")
      (node (ref "DISP1") (pin "18") (pinfunction "F_18") (pintype "passive"))
      (node (ref "DISP2") (pin "18") (pinfunction "F_18") (pintype "passive"))
      (node (ref "R4") (pin "2") (pinfunction "2_2") (pintype "passive"))
    )
    (net (code "49") (name "Net-(DISP1-G)") (class "Default")
      (node (ref "DISP1") (pin "17") (pinfunction "G_17") (pintype "passive"))
      (node (ref "DISP2") (pin "17") (pinfunction "G_17") (pintype "passive"))
      (node (ref "R5") (pin "2") (pinfunction "2_2") (pintype "passive"))
    )
    (net (code "50") (name "Net-(DISP1-H)") (class "Default")
      (node (ref "DISP1") (pin "15") (pinfunction "H_15") (pintype "passive"))
      (node (ref "DISP2") (pin "15") (pinfunction "H_15") (pintype "passive"))
      (node (ref "R6") (pin "2") (pinfunction "2_2") (pintype "passive"))
    )
    (net (code "51") (name "Net-(DISP1-J)") (class "Default")
      (node (ref "DISP1") (pin "14") (pinfunction "J_14") (pintype "passive"))
      (node (ref "DISP2") (pin "14") (pinfunction "J_14") (pintype "passive"))
      (node (ref "R7") (pin "2") (pinfunction "2_2") (pintype "passive"))
    )
    (net (code "52") (name "Net-(DISP1-K)") (class "Default")
      (node (ref "DISP1") (pin "6") (pinfunction "K_6") (pintype "passive"))
      (node (ref "DISP2") (pin "6") (pinfunction "K_6") (pintype "passive"))
      (node (ref "R17") (pin "2") (pinfunction "2_2") (pintype "passive"))
    )
    (net (code "53") (name "Net-(DISP1-K1)") (class "Default")
      (node (ref "DISP1") (pin "16") (pinfunction "K1_16") (pintype "passive"))
      (node (ref "Q1") (pin "C") (pinfunction "C_C") (pintype "passive"))
    )
    (net (code "54") (name "Net-(DISP1-K2)") (class "Default")
      (node (ref "DISP1") (pin "11") (pinfunction "K2_11") (pintype "passive"))
      (node (ref "Q2") (pin "C") (pinfunction "C_C") (pintype "passive"))
    )
    (net (code "55") (name "Net-(DISP1-L)") (class "Default")
      (node (ref "DISP1") (pin "5") (pinfunction "L_5") (pintype "passive"))
      (node (ref "DISP2") (pin "5") (pinfunction "L_5") (pintype "passive"))
      (node (ref "R16") (pin "2") (pinfunction "2_2") (pintype "passive"))
    )
    (net (code "56") (name "Net-(DISP1-M)") (class "Default")
      (node (ref "DISP1") (pin "4") (pinfunction "M_4") (pintype "passive"))
      (node (ref "DISP2") (pin "4") (pinfunction "M_4") (pintype "passive"))
      (node (ref "R15") (pin "2") (pinfunction "2_2") (pintype "passive"))
    )
    (net (code "57") (name "Net-(DISP1-N)") (class "Default")
      (node (ref "DISP1") (pin "2") (pinfunction "N_2") (pintype "passive"))
      (node (ref "DISP2") (pin "2") (pinfunction "N_2") (pintype "passive"))
      (node (ref "R14") (pin "2") (pinfunction "2_2") (pintype "passive"))
    )
    (net (code "58") (name "Net-(DISP1-P)") (class "Default")
      (node (ref "DISP1") (pin "13") (pinfunction "P_13") (pintype "passive"))
      (node (ref "DISP2") (pin "13") (pinfunction "P_13") (pintype "passive"))
      (node (ref "R8") (pin "2") (pinfunction "2_2") (pintype "passive"))
    )
    (net (code "59") (name "Net-(DISP2-K1)") (class "Default")
      (node (ref "DISP2") (pin "16") (pinfunction "K1_16") (pintype "passive"))
      (node (ref "Q3") (pin "C") (pinfunction "C_C") (pintype "passive"))
    )
    (net (code "60") (name "Net-(DISP2-K2)") (class "Default")
      (node (ref "DISP2") (pin "11") (pinfunction "K2_11") (pintype "passive"))
      (node (ref "Q4") (pin "C") (pinfunction "C_C") (pintype "passive"))
    )
    (net (code "61") (name "Net-(FM-Pad1)") (class "Default")
      (node (ref "FM") (pin "1") (pinfunction "1_1") (pintype "passive"))
      (node (ref "R23") (pin "1") (pinfunction "1_1") (pintype "passive"))
    )
    (net (code "62") (name "Net-(FM-Pad2)") (class "Default")
      (node (ref "FM") (pin "2") (pinfunction "2_2") (pintype "passive"))
      (node (ref "R50") (pin "1") (pinfunction "1_1") (pintype "passive"))
    )
    (net (code "63") (name "Net-(FM_ATT-Pad2)") (class "Default")
      (node (ref "FM_ATT") (pin "2") (pinfunction "2_2") (pintype "passive"))
      (node (ref "R23") (pin "2") (pinfunction "2_2") (pintype "passive"))
    )
    (net (code "64") (name "Net-(GATE_IN-Pad1)") (class "Default")
      (node (ref "GATE_IN") (pin "1") (pinfunction "1_1") (pintype "passive"))
      (node (ref "R28") (pin "1") (pinfunction "1_1") (pintype "passive"))
    )
    (net (code "65") (name "Net-(IC1A-QA)") (class "Default")
      (node (ref "IC1") (pin "15") (pinfunction "QA_15") (pintype "tri_state"))
      (node (ref "R7") (pin "1") (pinfunction "1_1") (pintype "passive"))
    )
    (net (code "66") (name "Net-(IC1A-QB)") (class "Default")
      (node (ref "IC1") (pin "1") (pinfunction "QB_1") (pintype "tri_state"))
      (node (ref "R17") (pin "1") (pinfunction "1_1") (pintype "passive"))
    )
    (net (code "67") (name "Net-(IC1A-QC)") (class "Default")
      (node (ref "IC1") (pin "2") (pinfunction "QC_2") (pintype "tri_state"))
      (node (ref "R16") (pin "1") (pinfunction "1_1") (pintype "passive"))
    )
    (net (code "68") (name "Net-(IC1A-QD)") (class "Default")
      (node (ref "IC1") (pin "3") (pinfunction "QD_3") (pintype "tri_state"))
      (node (ref "R15") (pin "1") (pinfunction "1_1") (pintype "passive"))
    )
    (net (code "69") (name "Net-(IC1A-QE)") (class "Default")
      (node (ref "IC1") (pin "4") (pinfunction "QE_4") (pintype "tri_state"))
      (node (ref "R14") (pin "1") (pinfunction "1_1") (pintype "passive"))
    )
    (net (code "70") (name "Net-(IC1A-QF)") (class "Default")
      (node (ref "IC1") (pin "5") (pinfunction "QF_5") (pintype "tri_state"))
      (node (ref "R8") (pin "1") (pinfunction "1_1") (pintype "passive"))
    )
    (net (code "71") (name "Net-(IC1A-SER)") (class "Default")
      (node (ref "IC1") (pin "14") (pinfunction "SER_14") (pintype "input"))
      (node (ref "IC2") (pin "9") (pinfunction "QH*_9") (pintype "tri_state"))
    )
    (net (code "72") (name "Net-(IC2A-QA)") (class "Default")
      (node (ref "IC2") (pin "15") (pinfunction "QA_15") (pintype "tri_state"))
      (node (ref "R9") (pin "1") (pinfunction "1_1") (pintype "passive"))
    )
    (net (code "73") (name "Net-(IC2A-QB)") (class "Default")
      (node (ref "IC2") (pin "1") (pinfunction "QB_1") (pintype "tri_state"))
      (node (ref "R10") (pin "1") (pinfunction "1_1") (pintype "passive"))
    )
    (net (code "74") (name "Net-(IC2A-QC)") (class "Default")
      (node (ref "IC2") (pin "2") (pinfunction "QC_2") (pintype "tri_state"))
      (node (ref "R12") (pin "1") (pinfunction "1_1") (pintype "passive"))
    )
    (net (code "75") (name "Net-(IC2A-QD)") (class "Default")
      (node (ref "IC2") (pin "3") (pinfunction "QD_3") (pintype "tri_state"))
      (node (ref "R18") (pin "1") (pinfunction "1_1") (pintype "passive"))
    )
    (net (code "76") (name "Net-(IC2A-QE)") (class "Default")
      (node (ref "IC2") (pin "4") (pinfunction "QE_4") (pintype "tri_state"))
      (node (ref "R13") (pin "1") (pinfunction "1_1") (pintype "passive"))
    )
    (net (code "77") (name "Net-(IC2A-QF)") (class "Default")
      (node (ref "IC2") (pin "5") (pinfunction "QF_5") (pintype "tri_state"))
      (node (ref "R4") (pin "1") (pinfunction "1_1") (pintype "passive"))
    )
    (net (code "78") (name "Net-(IC2A-QG)") (class "Default")
      (node (ref "IC2") (pin "6") (pinfunction "QG_6") (pintype "tri_state"))
      (node (ref "R5") (pin "1") (pinfunction "1_1") (pintype "passive"))
    )
    (net (code "79") (name "Net-(IC2A-QH)") (class "Default")
      (node (ref "IC2") (pin "7") (pinfunction "QH_7") (pintype "tri_state"))
      (node (ref "R6") (pin "1") (pinfunction "1_1") (pintype "passive"))
    )
    (net (code "80") (name "Net-(IC7A--IN)") (class "Default")
      (node (ref "IC7") (pin "2") (pinfunction "-IN_2") (pintype "input"))
      (node (ref "R32") (pin "1") (pinfunction "1_1") (pintype "passive"))
      (node (ref "R34") (pin "2") (pinfunction "2_2") (pintype "passive"))
    )
    (net (code "81") (name "Net-(IC7B--IN)") (class "Default")
      (node (ref "C17") (pin "1") (pinfunction "1_1") (pintype "passive"))
      (node (ref "FM_ATT") (pin "1") (pinfunction "1_1") (pintype "passive"))
      (node (ref "IC7") (pin "6") (pinfunction "-IN_6") (pintype "input"))
      (node (ref "R33") (pin "1") (pinfunction "1_1") (pintype "passive"))
      (node (ref "R38") (pin "2") (pinfunction "2_2") (pintype "passive"))
    )
    (net (code "82") (name "Net-(IC7C--IN)") (class "Default")
      (node (ref "IC7") (pin "9") (pinfunction "-IN_9") (pintype "input"))
      (node (ref "R25") (pin "1") (pinfunction "1_1") (pintype "passive"))
      (node (ref "R31") (pin "2") (pinfunction "2_2") (pintype "passive"))
    )
    (net (code "83") (name "Net-(IC7D--IN)") (class "Default")
      (node (ref "C13") (pin "1") (pinfunction "1_1") (pintype "passive"))
      (node (ref "IC7") (pin "13") (pinfunction "-IN_13") (pintype "input"))
      (node (ref "PARAM1_ATT") (pin "1") (pinfunction "1_1") (pintype "passive"))
      (node (ref "R26") (pin "1") (pinfunction "1_1") (pintype "passive"))
      (node (ref "R29") (pin "2") (pinfunction "2_2") (pintype "passive"))
    )
    (net (code "84") (name "Net-(IC8A--IN)") (class "Default")
      (node (ref "FM_ATT") (pin "3") (pinfunction "3_3") (pintype "passive"))
      (node (ref "IC8") (pin "2") (pinfunction "-IN_2") (pintype "input"))
      (node (ref "R49") (pin "1") (pinfunction "1_1") (pintype "passive"))
      (node (ref "R50") (pin "2") (pinfunction "2_2") (pintype "passive"))
      (node (ref "R51") (pin "2") (pinfunction "2_2") (pintype "passive"))
    )
    (net (code "85") (name "Net-(IC8A-OUT)") (class "Default")
      (node (ref "IC8") (pin "1") (pinfunction "OUT_1") (pintype "output"))
      (node (ref "R38") (pin "1") (pinfunction "1_1") (pintype "passive"))
      (node (ref "R49") (pin "2") (pinfunction "2_2") (pintype "passive"))
    )
    (net (code "86") (name "Net-(IC8B--IN)") (class "Default")
      (node (ref "C25") (pin "1") (pinfunction "1_1") (pintype "passive"))
      (node (ref "IC8") (pin "6") (pinfunction "-IN_6") (pintype "input"))
      (node (ref "R48") (pin "1") (pinfunction "1_1") (pintype "passive"))
      (node (ref "R52") (pin "2") (pinfunction "2_2") (pintype "passive"))
      (node (ref "R53") (pin "2") (pinfunction "2_2") (pintype "passive"))
    )
    (net (code "87") (name "Net-(IC8B-OUT)") (class "Default")
      (node (ref "C25") (pin "2") (pinfunction "2_2") (pintype "passive"))
      (node (ref "IC8") (pin "7") (pinfunction "OUT_7") (pintype "output"))
      (node (ref "R34") (pin "1") (pinfunction "1_1") (pintype "passive"))
      (node (ref "R48") (pin "2") (pinfunction "2_2") (pintype "passive"))
    )
    (net (code "88") (name "Net-(IC8C--IN)") (class "Default")
      (node (ref "C19") (pin "1") (pinfunction "1_1") (pintype "passive"))
      (node (ref "IC8") (pin "9") (pinfunction "-IN_9") (pintype "input"))
      (node (ref "R40") (pin "2") (pinfunction "2_2") (pintype "passive"))
      (node (ref "R41") (pin "1") (pinfunction "1_1") (pintype "passive"))
      (node (ref "R44") (pin "2") (pinfunction "2_2") (pintype "passive"))
    )
    (net (code "89") (name "Net-(IC8C-OUT)") (class "Default")
      (node (ref "C19") (pin "2") (pinfunction "2_2") (pintype "passive"))
      (node (ref "IC8") (pin "8") (pinfunction "OUT_8") (pintype "output"))
      (node (ref "R31") (pin "1") (pinfunction "1_1") (pintype "passive"))
      (node (ref "R41") (pin "2") (pinfunction "2_2") (pintype "passive"))
    )
    (net (code "90") (name "Net-(IC8D--IN)") (class "Default")
      (node (ref "IC8") (pin "13") (pinfunction "-IN_13") (pintype "input"))
      (node (ref "PARAM1_ATT") (pin "3") (pinfunction "3_3") (pintype "passive"))
      (node (ref "R39") (pin "1") (pinfunction "1_1") (pintype "passive"))
      (node (ref "R45") (pin "2") (pinfunction "2_2") (pintype "passive"))
    )
    (net (code "91") (name "Net-(IC8D-OUT)") (class "Default")
      (node (ref "IC8") (pin "14") (pinfunction "OUT_14") (pintype "output"))
      (node (ref "R29") (pin "1") (pinfunction "1_1") (pintype "passive"))
      (node (ref "R39") (pin "2") (pinfunction "2_2") (pintype "passive"))
    )
    (net (code "92") (name "Net-(IC9'A--IN)") (class "Default")
      (node (ref "C28'") (pin "1") (pinfunction "1_1") (pintype "passive"))
      (node (ref "IC9'") (pin "2") (pinfunction "-IN_2") (pintype "input"))
      (node (ref "R47'") (pin "2") (pinfunction "2_2") (pintype "passive"))
      (node (ref "R55'") (pin "1") (pinfunction "1_1") (pintype "passive"))
    )
    (net (code "93") (name "Net-(IC9'A-OUT)") (class "Default")
      (node (ref "C28'") (pin "2") (pinfunction "2_2") (pintype "passive"))
      (node (ref "IC9'") (pin "1") (pinfunction "OUT_1") (pintype "output"))
      (node (ref "R54'") (pin "1") (pinfunction "1_1") (pintype "passive"))
    )
    (net (code "94") (name "Net-(IC9'B-+IN)") (class "Default")
      (node (ref "C21'") (pin "1") (pinfunction "1_1") (pintype "passive"))
      (node (ref "IC9'") (pin "5") (pinfunction "+IN_5") (pintype "input"))
      (node (ref "R43'") (pin "2") (pinfunction "2_2") (pintype "passive"))
    )
    (net (code "95") (name "Net-(IC9'B--IN)") (class "Default")
      (node (ref "C20'") (pin "2") (pinfunction "2_2") (pintype "passive"))
      (node (ref "C23'") (pin "+") (pinfunction "+_+") (pintype "passive"))
      (node (ref "IC9'") (pin "6") (pinfunction "-IN_6") (pintype "input"))
      (node (ref "IC9'") (pin "7") (pinfunction "OUT_7") (pintype "output"))
    )
    (net (code "96") (name "Net-(IC9A--IN)") (class "Default")
      (node (ref "C28") (pin "1") (pinfunction "1_1") (pintype "passive"))
      (node (ref "IC9") (pin "2") (pinfunction "-IN_2") (pintype "input"))
      (node (ref "R47") (pin "2") (pinfunction "2_2") (pintype "passive"))
      (node (ref "R55") (pin "1") (pinfunction "1_1") (pintype "passive"))
    )
    (net (code "97") (name "Net-(IC9A-OUT)") (class "Default")
      (node (ref "C28") (pin "2") (pinfunction "2_2") (pintype "passive"))
      (node (ref "IC9") (pin "1") (pinfunction "OUT_1") (pintype "output"))
      (node (ref "R54") (pin "1") (pinfunction "1_1") (pintype "passive"))
    )
    (net (code "98") (name "Net-(IC9B-+IN)") (class "Default")
      (node (ref "C21") (pin "1") (pinfunction "1_1") (pintype "passive"))
      (node (ref "IC9") (pin "5") (pinfunction "+IN_5") (pintype "input"))
      (node (ref "R43") (pin "2") (pinfunction "2_2") (pintype "passive"))
    )
    (net (code "99") (name "Net-(IC9B--IN)") (class "Default")
      (node (ref "C20") (pin "2") (pinfunction "2_2") (pintype "passive"))
      (node (ref "C23") (pin "+") (pinfunction "+_+") (pintype "passive"))
      (node (ref "IC9") (pin "6") (pinfunction "-IN_6") (pintype "input"))
      (node (ref "IC9") (pin "7") (pinfunction "OUT_7") (pintype "output"))
    )
    (net (code "100") (name "Net-(MCU-3V3-PadEXT2-5)") (class "Default")
      (node (ref "MCU") (pin "EXT2-5") (pinfunction "3V3_EXT2-5") (pintype "bidirectional"))
      (node (ref "VDD_595") (pin "3") (pinfunction "3_3") (pintype "passive"))
      (node (ref "VDD_DAC") (pin "3") (pinfunction "3_3") (pintype "passive"))
    )
    (net (code "101") (name "Net-(MCU-PA8)") (class "Default")
      (node (ref "GPIO_DIG") (pin "1") (pinfunction "1_1") (pintype "passive"))
      (node (ref "MCU") (pin "EXT1-2") (pinfunction "PA8_EXT1-2") (pintype "bidirectional"))
    )
    (net (code "102") (name "Net-(MCU-PA9)") (class "Default")
      (node (ref "GPIO_DIG") (pin "2") (pinfunction "2_2") (pintype "passive"))
      (node (ref "MCU") (pin "EXT1-4") (pinfunction "PA9_EXT1-4") (pintype "bidirectional"))
    )
    (net (code "103") (name "Net-(PARAM1-Pad1)") (class "Default")
      (node (ref "PARAM1") (pin "1") (pinfunction "1_1") (pintype "passive"))
      (node (ref "R46") (pin "1") (pinfunction "1_1") (pintype "passive"))
    )
    (net (code "104") (name "Net-(PARAM1-Pad2)") (class "Default")
      (node (ref "PARAM1") (pin "2") (pinfunction "2_2") (pintype "passive"))
      (node (ref "R45") (pin "1") (pinfunction "1_1") (pintype "passive"))
    )
    (net (code "105") (name "Net-(PARAM1_ATT-Pad2)") (class "Default")
      (node (ref "PARAM1_ATT") (pin "2") (pinfunction "2_2") (pintype "passive"))
      (node (ref "R46") (pin "2") (pinfunction "2_2") (pintype "passive"))
    )
    (net (code "106") (name "Net-(PARAM2-Pad1)") (class "Default")
      (node (ref "PARAM2") (pin "1") (pinfunction "1_1") (pintype "passive"))
      (node (ref "R44") (pin "1") (pinfunction "1_1") (pintype "passive"))
    )
    (net (code "107") (name "Net-(PARAM2-Pad2)") (class "Default")
      (node (ref "PARAM2") (pin "2") (pinfunction "2_2") (pintype "passive"))
      (node (ref "R40") (pin "1") (pinfunction "1_1") (pintype "passive"))
    )
    (net (code "108") (name "Net-(PITCH-Pad1)") (class "Default")
      (node (ref "PITCH") (pin "1") (pinfunction "1_1") (pintype "passive"))
      (node (ref "R53") (pin "1") (pinfunction "1_1") (pintype "passive"))
    )
    (net (code "109") (name "Net-(PITCH-Pad2)") (class "Default")
      (node (ref "PITCH") (pin "2") (pinfunction "2_2") (pintype "passive"))
      (node (ref "R52") (pin "1") (pinfunction "1_1") (pintype "passive"))
    )
    (net (code "110") (name "Net-(Q1-PadB)") (class "Default")
      (node (ref "Q1") (pin "B") (pinfunction "B_B") (pintype "passive"))
      (node (ref "R1") (pin "2") (pinfunction "2_2") (pintype "passive"))
    )
    (net (code "111") (name "Net-(Q2-PadB)") (class "Default")
      (node (ref "Q2") (pin "B") (pinfunction "B_B") (pintype "passive"))
      (node (ref "R2") (pin "2") (pinfunction "2_2") (pintype "passive"))
    )
    (net (code "112") (name "Net-(Q3-PadB)") (class "Default")
      (node (ref "Q3") (pin "B") (pinfunction "B_B") (pintype "passive"))
      (node (ref "R3") (pin "2") (pinfunction "2_2") (pintype "passive"))
    )
    (net (code "113") (name "Net-(Q4-PadB)") (class "Default")
      (node (ref "Q4") (pin "B") (pinfunction "B_B") (pintype "passive"))
      (node (ref "R11") (pin "2") (pinfunction "2_2") (pintype "passive"))
    )
    (net (code "114") (name "Net-(Q6-PadB)") (class "Default")
      (node (ref "Q6") (pin "B") (pinfunction "B_B") (pintype "passive"))
      (node (ref "R28") (pin "2") (pinfunction "2_2") (pintype "passive"))
    )
    (net (code "115") (name "OUT_A") (class "Default")
      (node (ref "AUDIO_OUT") (pin "1") (pinfunction "1_1") (pintype "passive"))
      (node (ref "R54") (pin "2") (pinfunction "2_2") (pintype "passive"))
      (node (ref "R55") (pin "2") (pinfunction "2_2") (pintype "passive"))
    )
    (net (code "116") (name "OUT_B") (class "Default")
      (node (ref "AUDIO_OUT") (pin "3") (pinfunction "3_3") (pintype "passive"))
      (node (ref "R54'") (pin "2") (pinfunction "2_2") (pintype "passive"))
      (node (ref "R55'") (pin "2") (pinfunction "2_2") (pintype "passive"))
    )
    (net (code "117") (name "PARAM1_CV") (class "Default")
      (node (ref "C13") (pin "2") (pinfunction "2_2") (pintype "passive"))
      (node (ref "IC4") (pin "1") (pinfunction "CH0_1") (pintype "bidirectional"))
      (node (ref "IC7") (pin "14") (pinfunction "OUT_14") (pintype "output"))
      (node (ref "R26") (pin "2") (pinfunction "2_2") (pintype "passive"))
    )
    (net (code "118") (name "PARAM2_CV") (class "Default")
      (node (ref "IC4") (pin "2") (pinfunction "CH1_2") (pintype "bidirectional"))
      (node (ref "IC7") (pin "8") (pinfunction "OUT_8") (pintype "output"))
      (node (ref "R25") (pin "2") (pinfunction "2_2") (pintype "passive"))
    )
    (net (code "119") (name "PITCH_CV") (class "Default")
      (node (ref "IC4") (pin "3") (pinfunction "CH2_3") (pintype "bidirectional"))
      (node (ref "IC7") (pin "1") (pinfunction "OUT_1") (pintype "output"))
      (node (ref "R32") (pin "2") (pinfunction "2_2") (pintype "passive"))
    )
    (net (code "120") (name "VCC") (class "Default")
      (node (ref "C16") (pin "+") (pinfunction "+_+") (pintype "passive"))
      (node (ref "C22") (pin "1") (pinfunction "1_1") (pintype "passive"))
      (node (ref "C22'") (pin "1") (pinfunction "1_1") (pintype "passive"))
      (node (ref "C24") (pin "+") (pinfunction "+_+") (pintype "passive"))
      (node (ref "C27") (pin "1") (pinfunction "1_1") (pintype "passive"))
      (node (ref "D1") (pin "C") (pinfunction "C_C") (pintype "passive"))
      (node (ref "IC6") (pin "1") (pinfunction "VI_1") (pintype "input"))
      (node (ref "IC8") (pin "4") (pinfunction "V+_4") (pintype "power_in"))
      (node (ref "IC9") (pin "8") (pinfunction "V+_8") (pintype "power_in"))
      (node (ref "IC9'") (pin "8") (pinfunction "V+_8") (pintype "power_in"))
      (node (ref "R51") (pin "1") (pinfunction "1_1") (pintype "passive"))
      (node (ref "VCCVEE") (pin "1") (pinfunction "1_1") (pintype "passive"))
    )
    (net (code "121") (name "VDDA") (class "Default")
      (node (ref "AVOLT") (pin "1") (pinfunction "1_1") (pintype "passive"))
      (node (ref "C15") (pin "1") (pinfunction "1_1") (pintype "passive"))
      (node (ref "IC7") (pin "4") (pinfunction "V+_4") (pintype "power_in"))
      (node (ref "MCU") (pin "EXT2-1") (pinfunction "VDDA_EXT2-1") (pintype "bidirectional"))
      (node (ref "R22") (pin "2") (pinfunction "2_2") (pintype "passive"))
    )
    (net (code "122") (name "VDD_595") (class "Default")
      (node (ref "C1") (pin "1") (pinfunction "1_1") (pintype "passive"))
      (node (ref "C2") (pin "1") (pinfunction "1_1") (pintype "passive"))
      (node (ref "IC1") (pin "10") (pinfunction "SCL_10") (pintype "input"))
      (node (ref "IC1") (pin "16") (pinfunction "VCC_16") (pintype "power_in"))
      (node (ref "IC2") (pin "10") (pinfunction "SCL_10") (pintype "input"))
      (node (ref "IC2") (pin "16") (pinfunction "VCC_16") (pintype "power_in"))
      (node (ref "VDD_595") (pin "2") (pinfunction "2_2") (pintype "passive"))
    )
    (net (code "123") (name "VDD_ADC") (class "Default")
      (node (ref "5V-ADC-3V3") (pin "2") (pinfunction "2_2") (pintype "passive"))
      (node (ref "C6") (pin "1") (pinfunction "1_1") (pintype "passive"))
      (node (ref "C7") (pin "1") (pinfunction "1_1") (pintype "passive"))
      (node (ref "IC4") (pin "16") (pinfunction "VDD_16") (pintype "bidirectional"))
    )
    (net (code "124") (name "VDD_DAC") (class "Default")
      (node (ref "C11") (pin "1") (pinfunction "1_1") (pintype "passive"))
      (node (ref "C12") (pin "1") (pinfunction "1_1") (pintype "passive"))
      (node (ref "DAC_ADAPTER") (pin "P$1") (pinfunction "1_P$1") (pintype "bidirectional"))
      (node (ref "IC5") (pin "1") (pinfunction "VDD_1") (pintype "power_in"))
      (node (ref "VDD_DAC") (pin "2") (pinfunction "2_2") (pintype "passive"))
    )
    (net (code "125") (name "VEE") (class "Default")
      (node (ref "C18") (pin "2") (pinfunction "2_2") (pintype "passive"))
      (node (ref "C26") (pin "2") (pinfunction "2_2") (pintype "passive"))
      (node (ref "C26'") (pin "2") (pinfunction "2_2") (pintype "passive"))
      (node (ref "C29") (pin "-") (pinfunction "-_-") (pintype "passive"))
      (node (ref "D2") (pin "A") (pinfunction "A_A") (pintype "passive"))
      (node (ref "IC8") (pin "11") (pinfunction "V-_11") (pintype "power_in"))
      (node (ref "IC9") (pin "4") (pinfunction "V-_4") (pintype "power_in"))
      (node (ref "IC9'") (pin "4") (pinfunction "V-_4") (pintype "power_in"))
      (node (ref "VCCVEE") (pin "3") (pinfunction "3_3") (pintype "passive"))
    )
    (net (code "126") (name "unconnected-(DISP1-DP-Pad8)") (class "Default")
      (node (ref "DISP1") (pin "8") (pinfunction "DP_8") (pintype "passive"))
    )
    (net (code "127") (name "unconnected-(DISP2-DP-Pad8)") (class "Default")
      (node (ref "DISP2") (pin "8") (pinfunction "DP_8") (pintype "passive"))
    )
    (net (code "128") (name "unconnected-(IC1A-QG-Pad6)") (class "Default")
      (node (ref "IC1") (pin "6") (pinfunction "QG_6") (pintype "tri_state"))
    )
    (net (code "129") (name "unconnected-(IC1A-QH*-Pad9)") (class "Default")
      (node (ref "IC1") (pin "9") (pinfunction "QH*_9") (pintype "tri_state"))
    )
    (net (code "130") (name "unconnected-(IC1A-QH-Pad7)") (class "Default")
      (node (ref "IC1") (pin "7") (pinfunction "QH_7") (pintype "tri_state"))
    )
    (net (code "131") (name "unconnected-(MCU-NRST-PadEXT1-25)") (class "Default")
      (node (ref "MCU") (pin "EXT1-25") (pinfunction "NRST_EXT1-25") (pintype "bidirectional"))
    )
    (net (code "132") (name "unconnected-(MCU-PA0-PadEXT2-4)") (class "Default")
      (node (ref "MCU") (pin "EXT2-4") (pinfunction "PA0_EXT2-4") (pintype "bidirectional"))
    )
    (net (code "133") (name "unconnected-(MCU-PA1-PadEXT2-8)") (class "Default")
      (node (ref "MCU") (pin "EXT2-8") (pinfunction "PA1_EXT2-8") (pintype "bidirectional"))
    )
    (net (code "134") (name "unconnected-(MCU-PA2-PadEXT2-7)") (class "Default")
      (node (ref "MCU") (pin "EXT2-7") (pinfunction "PA2_EXT2-7") (pintype "bidirectional"))
    )
    (net (code "135") (name "unconnected-(MCU-PA10-PadEXT1-7)") (class "Default")
      (node (ref "MCU") (pin "EXT1-7") (pinfunction "PA10_EXT1-7") (pintype "bidirectional"))
    )
    (net (code "136") (name "unconnected-(MCU-PA11-PadEXT1-1)") (class "Default")
      (node (ref "MCU") (pin "EXT1-1") (pinfunction "PA11_EXT1-1") (pintype "bidirectional"))
    )
    (net (code "137") (name "unconnected-(MCU-PA12-PadEXT1-3)") (class "Default")
      (node (ref "MCU") (pin "EXT1-3") (pinfunction "PA12_EXT1-3") (pintype "bidirectional"))
    )
    (net (code "138") (name "unconnected-(MCU-PB10-PadEXT2-14)") (class "Default")
      (node (ref "MCU") (pin "EXT2-14") (pinfunction "PB10_EXT2-14") (pintype "bidirectional"))
    )
    (net (code "139") (name "unconnected-(MCU-PB11-PadEXT2-15)") (class "Default")
      (node (ref "MCU") (pin "EXT2-15") (pinfunction "PB11_EXT2-15") (pintype "bidirectional"))
    )
    (net (code "140") (name "unconnected-(MCU-PB14-PadEXT2-18)") (class "Default")
      (node (ref "MCU") (pin "EXT2-18") (pinfunction "PB14_EXT2-18") (pintype "bidirectional"))
    )
    (net (code "141") (name "unconnected-(MCU-PC2-PadEXT2-2)") (class "Default")
      (node (ref "MCU") (pin "EXT2-2") (pinfunction "PC2_EXT2-2") (pintype "bidirectional"))
    )
    (net (code "142") (name "unconnected-(MCU-PC3-PadEXT2-9)") (class "Default")
      (node (ref "MCU") (pin "EXT2-9") (pinfunction "PC3_EXT2-9") (pintype "bidirectional"))
    )
    (net (code "143") (name "unconnected-(MCU-PC6-PadEXT2-20)") (class "Default")
      (node (ref "MCU") (pin "EXT2-20") (pinfunction "PC6_EXT2-20") (pintype "bidirectional"))
    )
    (net (code "144") (name "unconnected-(MCU-PC7-PadEXT2-21)") (class "Default")
      (node (ref "MCU") (pin "EXT2-21") (pinfunction "PC7_EXT2-21") (pintype "bidirectional"))
    )
    (net (code "145") (name "unconnected-(MCU-PC11-PadEXT1-9)") (class "Default")
      (node (ref "MCU") (pin "EXT1-9") (pinfunction "PC11_EXT1-9") (pintype "bidirectional"))
    )
    (net (code "146") (name "unconnected-(MCU-PD2-PadEXT1-11)") (class "Default")
      (node (ref "MCU") (pin "EXT1-11") (pinfunction "PD2_EXT1-11") (pintype "bidirectional"))
    )
    (net (code "147") (name "unconnected-(MCU-VBAT-PadEXT1-23)") (class "Default")
      (node (ref "MCU") (pin "EXT1-23") (pinfunction "VBAT_EXT1-23") (pintype "bidirectional"))
    )
    (net (code "148") (name "unconnected-(MCU-VUSB-PadEXT2-23)") (class "Default")
      (node (ref "MCU") (pin "EXT2-23") (pinfunction "VUSB_EXT2-23") (pintype "bidirectional"))
    )
  )
)
